# out_8x_16A_bistab_4MU_v2_1.net
KiCad netlist of a schematic drawn in EAGLE
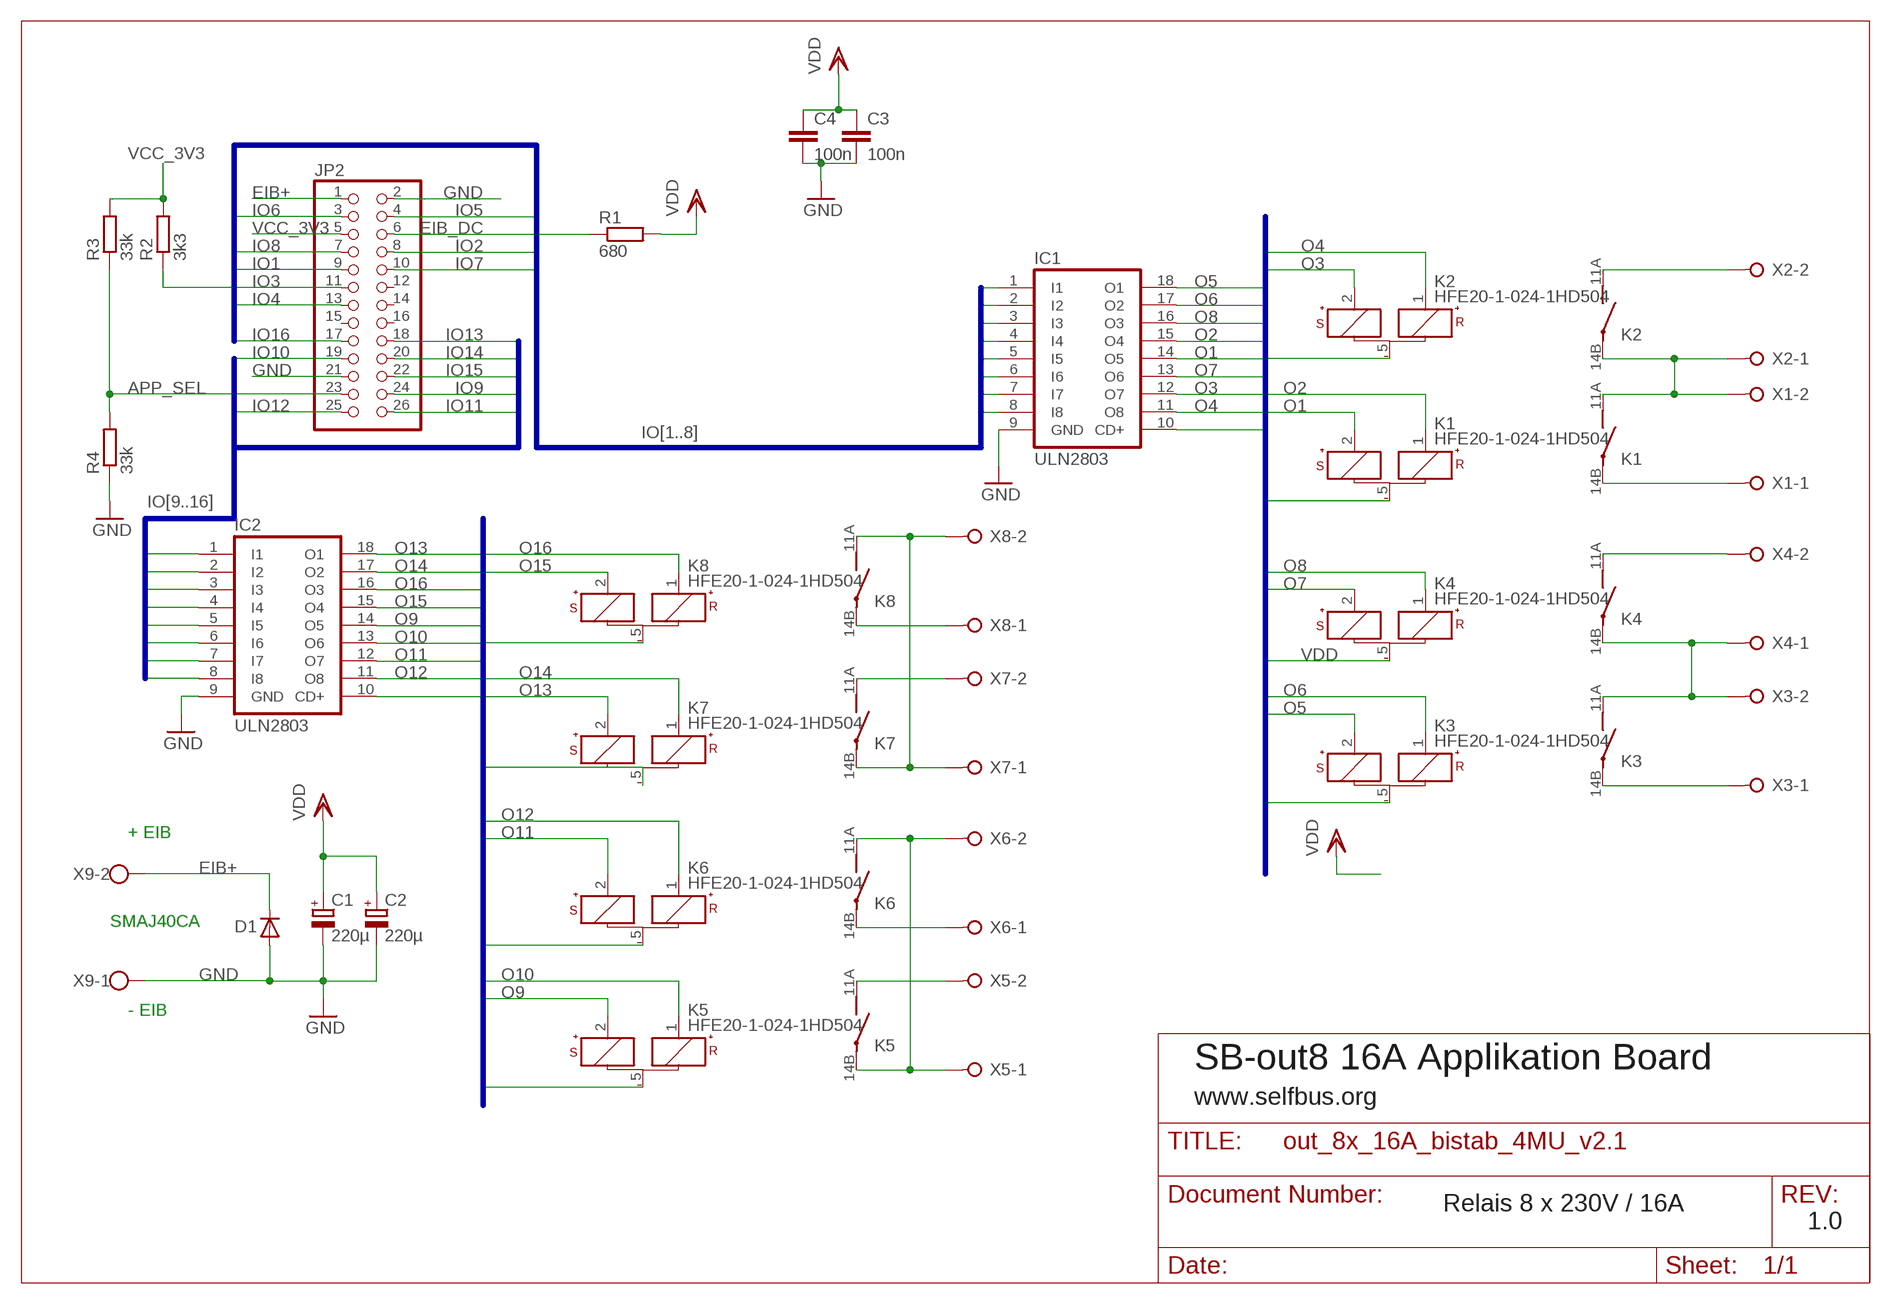
[diagram p0: schematic, sheet 1]

(export (version "E")
  (design (tool "Eeschema 10.0.6"))
  (components
    (comp (ref "C1")
      (value "220µ")
      (footprint "eagle-import:E3,5-8")
      (libsource (lib "eagle-import") (part "CPOL-EUE3.5-8"))
    )
    (comp (ref "C2")
      (value "220µ")
      (footprint "eagle-import:E3,5-8")
      (libsource (lib "eagle-import") (part "CPOL-EUE3.5-8"))
    )
    (comp (ref "C3")
      (value "100n")
      (footprint "eagle-import:C1206")
      (libsource (lib "eagle-import") (part "C-EUC1206"))
    )
    (comp (ref "C4")
      (value "100n")
      (footprint "eagle-import:C1206")
      (libsource (lib "eagle-import") (part "C-EUC1206"))
    )
    (comp (ref "D1")
      (value "D-SMB")
      (footprint "eagle-import:SMB")
      (libsource (lib "eagle-import") (part "D-SMB"))
    )
    (comp (ref "IC1")
      (value "ULN2803")
      (footprint "eagle-import:SO18W")
      (libsource (lib "eagle-import") (part "ULN2803ASOP18"))
    )
    (comp (ref "IC2")
      (value "ULN2803")
      (footprint "eagle-import:SO18W")
      (libsource (lib "eagle-import") (part "ULN2803ASOP18"))
    )
    (comp (ref "JP2")
      (value "PINHD-2X13_2.54-SMD")
      (footprint "eagle-import:2X13SMD")
      (libsource (lib "eagle-import") (part "PINHD-2X13_2.54-SMD"))
    )
    (comp (ref "K1")
      (value "HFE20-1-024-1HD504")
      (footprint "eagle-import:HFE20-3-504")
      (libsource (lib "eagle-import") (part "HFE20-1-024-1HD504"))
    )
    (comp (ref "K2")
      (value "HFE20-1-024-1HD504")
      (footprint "eagle-import:HFE20-3-504")
      (libsource (lib "eagle-import") (part "HFE20-1-024-1HD504"))
    )
    (comp (ref "K3")
      (value "HFE20-1-024-1HD504")
      (footprint "eagle-import:HFE20-3-504")
      (libsource (lib "eagle-import") (part "HFE20-1-024-1HD504"))
    )
    (comp (ref "K4")
      (value "HFE20-1-024-1HD504")
      (footprint "eagle-import:HFE20-3-504")
      (libsource (lib "eagle-import") (part "HFE20-1-024-1HD504"))
    )
    (comp (ref "K5")
      (value "HFE20-1-024-1HD504")
      (footprint "eagle-import:HFE20-3-504")
      (libsource (lib "eagle-import") (part "HFE20-1-024-1HD504"))
    )
    (comp (ref "K6")
      (value "HFE20-1-024-1HD504")
      (footprint "eagle-import:HFE20-3-504")
      (libsource (lib "eagle-import") (part "HFE20-1-024-1HD504"))
    )
    (comp (ref "K7")
      (value "HFE20-1-024-1HD504")
      (footprint "eagle-import:HFE20-3-504")
      (libsource (lib "eagle-import") (part "HFE20-1-024-1HD504"))
    )
    (comp (ref "K8")
      (value "HFE20-1-024-1HD504")
      (footprint "eagle-import:HFE20-3-504")
      (libsource (lib "eagle-import") (part "HFE20-1-024-1HD504"))
    )
    (comp (ref "R1")
      (value "680")
      (footprint "eagle-import:M1206")
      (libsource (lib "eagle-import") (part "R-EU_M1206"))
    )
    (comp (ref "R2")
      (value "3k3")
      (footprint "eagle-import:M1206")
      (libsource (lib "eagle-import") (part "R-EU_M1206"))
    )
    (comp (ref "R3")
      (value "33k")
      (footprint "eagle-import:M1206")
      (libsource (lib "eagle-import") (part "R-EU_M1206"))
    )
    (comp (ref "R4")
      (value "33k")
      (footprint "eagle-import:M1206")
      (libsource (lib "eagle-import") (part "R-EU_M1206"))
    )
    (comp (ref "X1")
      (value "W237-02P")
      (footprint "eagle-import:W237-132")
      (libsource (lib "eagle-import") (part "W237-02P"))
    )
    (comp (ref "X2")
      (value "W237-02P")
      (footprint "eagle-import:W237-132")
      (libsource (lib "eagle-import") (part "W237-02P"))
    )
    (comp (ref "X3")
      (value "W237-02P")
      (footprint "eagle-import:W237-132")
      (libsource (lib "eagle-import") (part "W237-02P"))
    )
    (comp (ref "X4")
      (value "W237-02P")
      (footprint "eagle-import:W237-132")
      (libsource (lib "eagle-import") (part "W237-02P"))
    )
    (comp (ref "X5")
      (value "W237-02P")
      (footprint "eagle-import:W237-132")
      (libsource (lib "eagle-import") (part "W237-02P"))
    )
    (comp (ref "X6")
      (value "W237-02P")
      (footprint "eagle-import:W237-132")
      (libsource (lib "eagle-import") (part "W237-02P"))
    )
    (comp (ref "X7")
      (value "W237-02P")
      (footprint "eagle-import:W237-132")
      (libsource (lib "eagle-import") (part "W237-02P"))
    )
    (comp (ref "X8")
      (value "W237-02P")
      (footprint "eagle-import:W237-132")
      (libsource (lib "eagle-import") (part "W237-02P"))
    )
    (comp (ref "X9")
      (value "W237-102")
      (footprint "eagle-import:W237-102")
      (libsource (lib "eagle-import") (part "W237-102"))
    )
  )
  (nets
    (net (code "1") (name "/APP_SEL") (class "Default")
      (node (ref "JP2") (pin "23") (pinfunction "23_23") (pintype "passive"))
      (node (ref "R3") (pin "1") (pinfunction "1_1") (pintype "passive"))
      (node (ref "R4") (pin "2") (pinfunction "2_2") (pintype "passive"))
    )
    (net (code "2") (name "/EIB+") (class "Default")
      (node (ref "D1") (pin "1") (pinfunction "C_1") (pintype "passive"))
      (node (ref "JP2") (pin "1") (pinfunction "1_1") (pintype "passive"))
      (node (ref "X9") (pin "2") (pinfunction "KL_2") (pintype "passive"))
    )
    (net (code "3") (name "/EIB_DC") (class "Default")
      (node (ref "JP2") (pin "6") (pinfunction "6_6") (pintype "passive"))
      (node (ref "R1") (pin "1") (pinfunction "1_1") (pintype "passive"))
    )
    (net (code "4") (name "/IO1") (class "Default")
      (node (ref "IC1") (pin "5") (pinfunction "I5_5") (pintype "input"))
      (node (ref "JP2") (pin "9") (pinfunction "9_9") (pintype "passive"))
    )
    (net (code "5") (name "/IO2") (class "Default")
      (node (ref "IC1") (pin "4") (pinfunction "I4_4") (pintype "input"))
      (node (ref "JP2") (pin "8") (pinfunction "8_8") (pintype "passive"))
    )
    (net (code "6") (name "/IO3") (class "Default")
      (node (ref "IC1") (pin "7") (pinfunction "I7_7") (pintype "input"))
      (node (ref "JP2") (pin "11") (pinfunction "11_11") (pintype "passive"))
      (node (ref "R2") (pin "1") (pinfunction "1_1") (pintype "passive"))
    )
    (net (code "7") (name "/IO4") (class "Default")
      (node (ref "IC1") (pin "8") (pinfunction "I8_8") (pintype "input"))
      (node (ref "JP2") (pin "13") (pinfunction "13_13") (pintype "passive"))
    )
    (net (code "8") (name "/IO5") (class "Default")
      (node (ref "IC1") (pin "1") (pinfunction "I1_1") (pintype "input"))
      (node (ref "JP2") (pin "4") (pinfunction "4_4") (pintype "passive"))
    )
    (net (code "9") (name "/IO6") (class "Default")
      (node (ref "IC1") (pin "2") (pinfunction "I2_2") (pintype "input"))
      (node (ref "JP2") (pin "3") (pinfunction "3_3") (pintype "passive"))
    )
    (net (code "10") (name "/IO7") (class "Default")
      (node (ref "IC1") (pin "6") (pinfunction "I6_6") (pintype "input"))
      (node (ref "JP2") (pin "10") (pinfunction "10_10") (pintype "passive"))
    )
    (net (code "11") (name "/IO8") (class "Default")
      (node (ref "IC1") (pin "3") (pinfunction "I3_3") (pintype "input"))
      (node (ref "JP2") (pin "7") (pinfunction "7_7") (pintype "passive"))
    )
    (net (code "12") (name "/IO9") (class "Default")
      (node (ref "IC2") (pin "5") (pinfunction "I5_5") (pintype "input"))
      (node (ref "JP2") (pin "24") (pinfunction "24_24") (pintype "passive"))
    )
    (net (code "13") (name "/IO10") (class "Default")
      (node (ref "IC2") (pin "6") (pinfunction "I6_6") (pintype "input"))
      (node (ref "JP2") (pin "19") (pinfunction "19_19") (pintype "passive"))
    )
    (net (code "14") (name "/IO11") (class "Default")
      (node (ref "IC2") (pin "7") (pinfunction "I7_7") (pintype "input"))
      (node (ref "JP2") (pin "26") (pinfunction "26_26") (pintype "passive"))
    )
    (net (code "15") (name "/IO12") (class "Default")
      (node (ref "IC2") (pin "8") (pinfunction "I8_8") (pintype "input"))
      (node (ref "JP2") (pin "25") (pinfunction "25_25") (pintype "passive"))
    )
    (net (code "16") (name "/IO13") (class "Default")
      (node (ref "IC2") (pin "1") (pinfunction "I1_1") (pintype "input"))
      (node (ref "JP2") (pin "18") (pinfunction "18_18") (pintype "passive"))
    )
    (net (code "17") (name "/IO14") (class "Default")
      (node (ref "IC2") (pin "2") (pinfunction "I2_2") (pintype "input"))
      (node (ref "JP2") (pin "20") (pinfunction "20_20") (pintype "passive"))
    )
    (net (code "18") (name "/IO15") (class "Default")
      (node (ref "IC2") (pin "4") (pinfunction "I4_4") (pintype "input"))
      (node (ref "JP2") (pin "22") (pinfunction "22_22") (pintype "passive"))
    )
    (net (code "19") (name "/IO16") (class "Default")
      (node (ref "IC2") (pin "3") (pinfunction "I3_3") (pintype "input"))
      (node (ref "JP2") (pin "17") (pinfunction "17_17") (pintype "passive"))
    )
    (net (code "22") (name "/O1") (class "Default")
      (node (ref "IC1") (pin "14") (pinfunction "O5_14") (pintype "open_collector"))
      (node (ref "K1") (pin "2") (pinfunction "S+_2") (pintype "passive"))
    )
    (net (code "23") (name "/O2") (class "Default")
      (node (ref "IC1") (pin "15") (pinfunction "O4_15") (pintype "open_collector"))
      (node (ref "K1") (pin "1") (pinfunction "R+_1") (pintype "passive"))
    )
    (net (code "24") (name "/O3") (class "Default")
      (node (ref "IC1") (pin "12") (pinfunction "O7_12") (pintype "open_collector"))
      (node (ref "K2") (pin "2") (pinfunction "S+_2") (pintype "passive"))
    )
    (net (code "25") (name "/O4") (class "Default")
      (node (ref "IC1") (pin "11") (pinfunction "O8_11") (pintype "open_collector"))
      (node (ref "K2") (pin "1") (pinfunction "R+_1") (pintype "passive"))
    )
    (net (code "26") (name "/O5") (class "Default")
      (node (ref "IC1") (pin "18") (pinfunction "O1_18") (pintype "open_collector"))
      (node (ref "K3") (pin "2") (pinfunction "S+_2") (pintype "passive"))
    )
    (net (code "27") (name "/O6") (class "Default")
      (node (ref "IC1") (pin "17") (pinfunction "O2_17") (pintype "open_collector"))
      (node (ref "K3") (pin "1") (pinfunction "R+_1") (pintype "passive"))
    )
    (net (code "28") (name "/O7") (class "Default")
      (node (ref "IC1") (pin "13") (pinfunction "O6_13") (pintype "open_collector"))
      (node (ref "K4") (pin "2") (pinfunction "S+_2") (pintype "passive"))
    )
    (net (code "29") (name "/O8") (class "Default")
      (node (ref "IC1") (pin "16") (pinfunction "O3_16") (pintype "open_collector"))
      (node (ref "K4") (pin "1") (pinfunction "R+_1") (pintype "passive"))
    )
    (net (code "30") (name "/O9") (class "Default")
      (node (ref "IC2") (pin "14") (pinfunction "O5_14") (pintype "open_collector"))
      (node (ref "K5") (pin "2") (pinfunction "S+_2") (pintype "passive"))
    )
    (net (code "31") (name "/O10") (class "Default")
      (node (ref "IC2") (pin "13") (pinfunction "O6_13") (pintype "open_collector"))
      (node (ref "K5") (pin "1") (pinfunction "R+_1") (pintype "passive"))
    )
    (net (code "32") (name "/O11") (class "Default")
      (node (ref "IC2") (pin "12") (pinfunction "O7_12") (pintype "open_collector"))
      (node (ref "K6") (pin "2") (pinfunction "S+_2") (pintype "passive"))
    )
    (net (code "33") (name "/O12") (class "Default")
      (node (ref "IC2") (pin "11") (pinfunction "O8_11") (pintype "open_collector"))
      (node (ref "K6") (pin "1") (pinfunction "R+_1") (pintype "passive"))
    )
    (net (code "34") (name "/O13") (class "Default")
      (node (ref "IC2") (pin "18") (pinfunction "O1_18") (pintype "open_collector"))
      (node (ref "K7") (pin "2") (pinfunction "S+_2") (pintype "passive"))
    )
    (net (code "35") (name "/O14") (class "Default")
      (node (ref "IC2") (pin "17") (pinfunction "O2_17") (pintype "open_collector"))
      (node (ref "K7") (pin "1") (pinfunction "R+_1") (pintype "passive"))
    )
    (net (code "36") (name "/O15") (class "Default")
      (node (ref "IC2") (pin "15") (pinfunction "O4_15") (pintype "open_collector"))
      (node (ref "K8") (pin "2") (pinfunction "S+_2") (pintype "passive"))
    )
    (net (code "37") (name "/O16") (class "Default")
      (node (ref "IC2") (pin "16") (pinfunction "O3_16") (pintype "open_collector"))
      (node (ref "K8") (pin "1") (pinfunction "R+_1") (pintype "passive"))
    )
    (net (code "38") (name "/VCC_3V3") (class "Default")
      (node (ref "JP2") (pin "5") (pinfunction "5_5") (pintype "passive"))
      (node (ref "R2") (pin "2") (pinfunction "2_2") (pintype "passive"))
      (node (ref "R3") (pin "2") (pinfunction "2_2") (pintype "passive"))
    )
    (net (code "39") (name "GND") (class "Default")
      (node (ref "C1") (pin "-") (pinfunction "-_-") (pintype "passive"))
      (node (ref "C2") (pin "-") (pinfunction "-_-") (pintype "passive"))
      (node (ref "C3") (pin "2") (pinfunction "2_2") (pintype "passive"))
      (node (ref "C4") (pin "2") (pinfunction "2_2") (pintype "passive"))
      (node (ref "D1") (pin "2") (pinfunction "A_2") (pintype "passive"))
      (node (ref "IC1") (pin "9") (pinfunction "GND_9") (pintype "power_in"))
      (node (ref "IC2") (pin "9") (pinfunction "GND_9") (pintype "power_in"))
      (node (ref "JP2") (pin "2") (pinfunction "2_2") (pintype "passive"))
      (node (ref "JP2") (pin "21") (pinfunction "21_21") (pintype "passive"))
      (node (ref "R4") (pin "1") (pinfunction "1_1") (pintype "passive"))
      (node (ref "X9") (pin "1") (pinfunction "KL_1") (pintype "passive"))
    )
    (net (code "40") (name "Net-(K1B-PA)") (class "Default")
      (node (ref "K1") (pin "14B") (pinfunction "PA_14B") (pintype "passive"))
      (node (ref "X1") (pin "1") (pinfunction "KL_1") (pintype "passive"))
    )
    (net (code "41") (name "Net-(K1B-PB)") (class "Default")
      (node (ref "K1") (pin "11A") (pinfunction "PB_11A") (pintype "passive"))
      (node (ref "K2") (pin "14B") (pinfunction "PA_14B") (pintype "passive"))
      (node (ref "X1") (pin "2") (pinfunction "KL_2") (pintype "passive"))
      (node (ref "X2") (pin "1") (pinfunction "KL_1") (pintype "passive"))
    )
    (net (code "42") (name "Net-(K2B-PB)") (class "Default")
      (node (ref "K2") (pin "11A") (pinfunction "PB_11A") (pintype "passive"))
      (node (ref "X2") (pin "2") (pinfunction "KL_2") (pintype "passive"))
    )
    (net (code "43") (name "Net-(K3B-PA)") (class "Default")
      (node (ref "K3") (pin "14B") (pinfunction "PA_14B") (pintype "passive"))
      (node (ref "X3") (pin "1") (pinfunction "KL_1") (pintype "passive"))
    )
    (net (code "44") (name "Net-(K3B-PB)") (class "Default")
      (node (ref "K3") (pin "11A") (pinfunction "PB_11A") (pintype "passive"))
      (node (ref "K4") (pin "14B") (pinfunction "PA_14B") (pintype "passive"))
      (node (ref "X3") (pin "2") (pinfunction "KL_2") (pintype "passive"))
      (node (ref "X4") (pin "1") (pinfunction "KL_1") (pintype "passive"))
    )
    (net (code "45") (name "Net-(K4B-PB)") (class "Default")
      (node (ref "K4") (pin "11A") (pinfunction "PB_11A") (pintype "passive"))
      (node (ref "X4") (pin "2") (pinfunction "KL_2") (pintype "passive"))
    )
    (net (code "46") (name "Net-(K5B-PA)") (class "Default")
      (node (ref "K5") (pin "14B") (pinfunction "PA_14B") (pintype "passive"))
      (node (ref "K6") (pin "11A") (pinfunction "PB_11A") (pintype "passive"))
      (node (ref "X5") (pin "1") (pinfunction "KL_1") (pintype "passive"))
      (node (ref "X6") (pin "2") (pinfunction "KL_2") (pintype "passive"))
    )
    (net (code "47") (name "Net-(K5B-PB)") (class "Default")
      (node (ref "K5") (pin "11A") (pinfunction "PB_11A") (pintype "passive"))
      (node (ref "X5") (pin "2") (pinfunction "KL_2") (pintype "passive"))
    )
    (net (code "48") (name "Net-(K6B-PA)") (class "Default")
      (node (ref "K6") (pin "14B") (pinfunction "PA_14B") (pintype "passive"))
      (node (ref "X6") (pin "1") (pinfunction "KL_1") (pintype "passive"))
    )
    (net (code "49") (name "Net-(K7B-PA)") (class "Default")
      (node (ref "K7") (pin "14B") (pinfunction "PA_14B") (pintype "passive"))
      (node (ref "K8") (pin "11A") (pinfunction "PB_11A") (pintype "passive"))
      (node (ref "X7") (pin "1") (pinfunction "KL_1") (pintype "passive"))
      (node (ref "X8") (pin "2") (pinfunction "KL_2") (pintype "passive"))
    )
    (net (code "50") (name "Net-(K7B-PB)") (class "Default")
      (node (ref "K7") (pin "11A") (pinfunction "PB_11A") (pintype "passive"))
      (node (ref "X7") (pin "2") (pinfunction "KL_2") (pintype "passive"))
    )
    (net (code "51") (name "Net-(K8B-PA)") (class "Default")
      (node (ref "K8") (pin "14B") (pinfunction "PA_14B") (pintype "passive"))
      (node (ref "X8") (pin "1") (pinfunction "KL_1") (pintype "passive"))
    )
    (net (code "52") (name "VDD") (class "Default")
      (node (ref "C1") (pin "+") (pinfunction "+_+") (pintype "passive"))
      (node (ref "C2") (pin "+") (pinfunction "+_+") (pintype "passive"))
      (node (ref "C3") (pin "1") (pinfunction "1_1") (pintype "passive"))
      (node (ref "C4") (pin "1") (pinfunction "1_1") (pintype "passive"))
      (node (ref "IC1") (pin "10") (pinfunction "CD+_10") (pintype "passive"))
      (node (ref "IC2") (pin "10") (pinfunction "CD+_10") (pintype "passive"))
      (node (ref "K1") (pin "5") (pinfunction "-_5") (pintype "passive"))
      (node (ref "K2") (pin "5") (pinfunction "-_5") (pintype "passive"))
      (node (ref "K3") (pin "5") (pinfunction "-_5") (pintype "passive"))
      (node (ref "K4") (pin "5") (pinfunction "-_5") (pintype "passive"))
      (node (ref "K5") (pin "5") (pinfunction "-_5") (pintype "passive"))
      (node (ref "K6") (pin "5") (pinfunction "-_5") (pintype "passive"))
      (node (ref "K7") (pin "5") (pinfunction "-_5") (pintype "passive"))
      (node (ref "K8") (pin "5") (pinfunction "-_5") (pintype "passive"))
      (node (ref "R1") (pin "2") (pinfunction "2_2") (pintype "passive"))
    )
    (net (code "53") (name "unconnected-(JP2-Pad12)") (class "Default")
      (node (ref "JP2") (pin "12") (pinfunction "12_12") (pintype "passive"))
    )
    (net (code "54") (name "unconnected-(JP2-Pad14)") (class "Default")
      (node (ref "JP2") (pin "14") (pinfunction "14_14") (pintype "passive"))
    )
    (net (code "55") (name "unconnected-(JP2-Pad15)") (class "Default")
      (node (ref "JP2") (pin "15") (pinfunction "15_15") (pintype "passive"))
    )
    (net (code "56") (name "unconnected-(JP2-Pad16)") (class "Default")
      (node (ref "JP2") (pin "16") (pinfunction "16_16") (pintype "passive"))
    )
  )
)
